# Bf706_DSP.net
KiCad netlist of a schematic drawn in Altium Designer
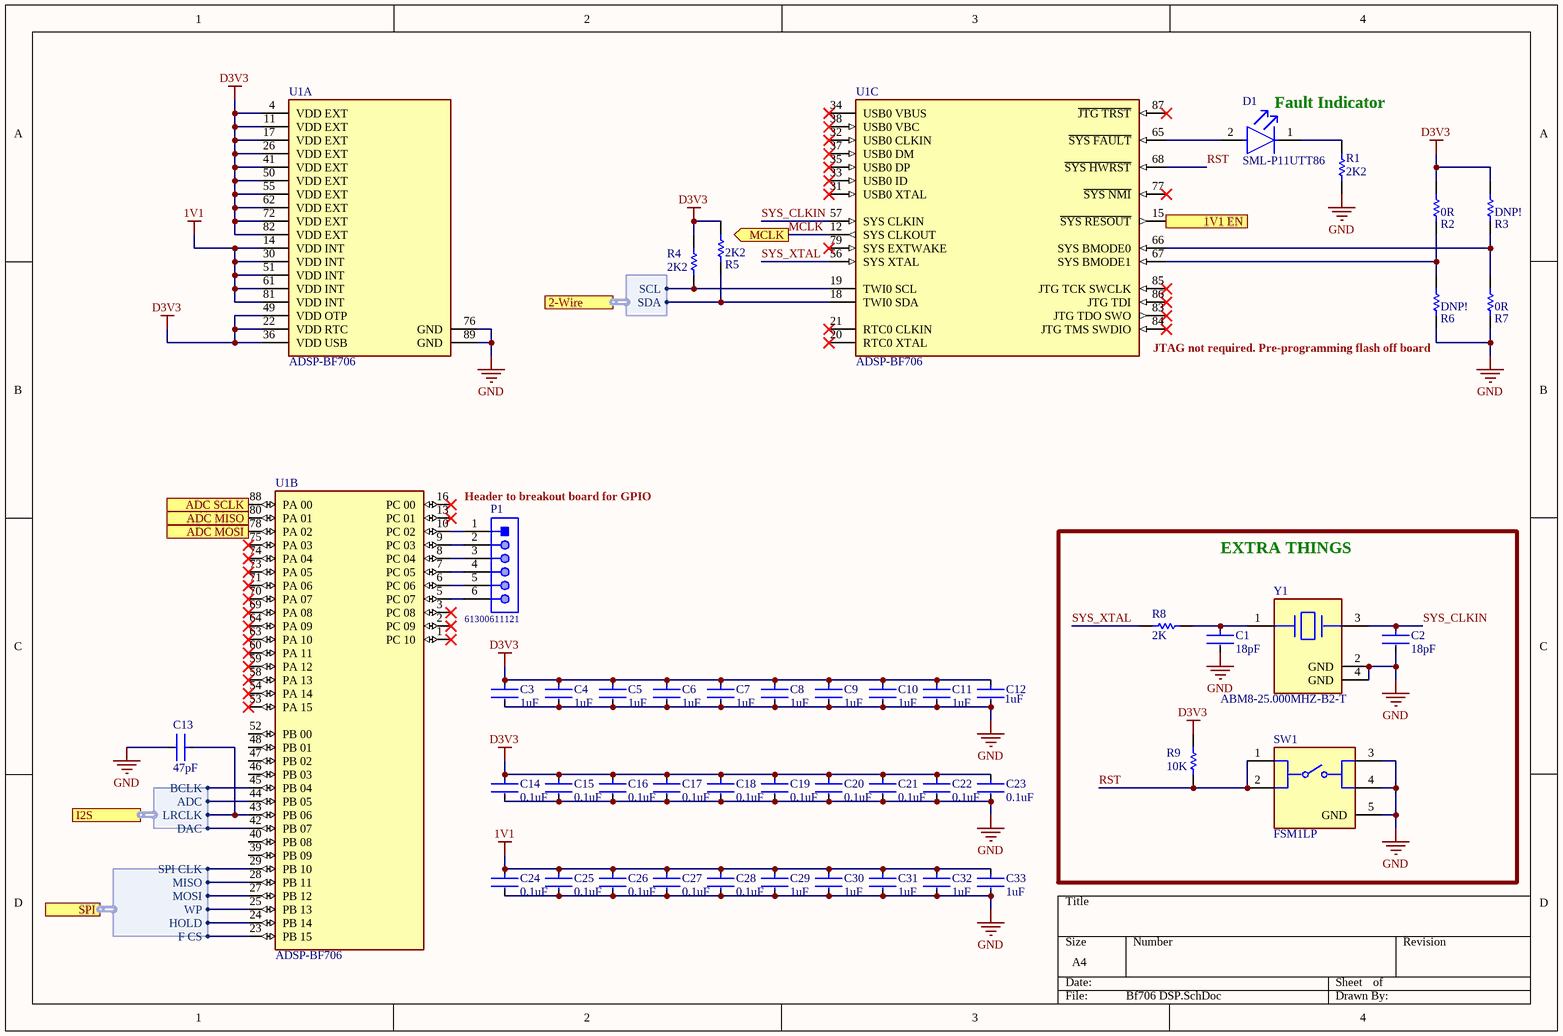
[diagram p0: Bf706 DSP.SchDoc]

(export (version "E")
  (design (tool "Eeschema 10.0.6"))
  (components
    (comp (ref "C1")
      (value "18pF")
      (footprint "FP-GRM15-MFG")
      (description "CAP CER 0.1UF 16V X7R 0402")
      (fields (field (name "MANUFACTURER PART NUMBER") "GRM155R71C104KA88D") (field (name "TOLERANCE") "10%"))
      (libsource (lib "Altium Content Vault") (part "236180d848d6139a670b325ea6854c9"))
    )
    (comp (ref "C2")
      (value "18pF")
      (footprint "FP-GRM15-MFG")
      (description "CAP CER 0.1UF 16V X7R 0402")
      (fields (field (name "MANUFACTURER PART NUMBER") "GRM155R71C104KA88D") (field (name "TOLERANCE") "10%"))
      (libsource (lib "Altium Content Vault") (part "236180d848d6139a670b325ea6854c9"))
    )
    (comp (ref "C3")
      (value "1uF")
      (footprint "FP-GRM15-MFG")
      (description "CAP CER 0.1UF 16V X7R 0402")
      (fields (field (name "MANUFACTURER PART NUMBER") "GRM155R71C104KA88D") (field (name "TOLERANCE") "10%"))
      (libsource (lib "Altium Content Vault") (part "236180d848d6139a670b325ea6854c9"))
    )
    (comp (ref "C4")
      (value "1uF")
      (footprint "FP-GRM15-MFG")
      (description "CAP CER 0.1UF 16V X7R 0402")
      (fields (field (name "MANUFACTURER PART NUMBER") "GRM155R71C104KA88D") (field (name "TOLERANCE") "10%"))
      (libsource (lib "Altium Content Vault") (part "236180d848d6139a670b325ea6854c9"))
    )
    (comp (ref "C5")
      (value "1uF")
      (footprint "FP-GRM15-MFG")
      (description "CAP CER 0.1UF 16V X7R 0402")
      (fields (field (name "MANUFACTURER PART NUMBER") "GRM155R71C104KA88D") (field (name "TOLERANCE") "10%"))
      (libsource (lib "Altium Content Vault") (part "236180d848d6139a670b325ea6854c9"))
    )
    (comp (ref "C6")
      (value "1uF")
      (footprint "FP-GRM15-MFG")
      (description "CAP CER 0.1UF 16V X7R 0402")
      (fields (field (name "MANUFACTURER PART NUMBER") "GRM155R71C104KA88D") (field (name "TOLERANCE") "10%"))
      (libsource (lib "Altium Content Vault") (part "236180d848d6139a670b325ea6854c9"))
    )
    (comp (ref "C7")
      (value "1uF")
      (footprint "FP-GRM15-MFG")
      (description "CAP CER 0.1UF 16V X7R 0402")
      (fields (field (name "MANUFACTURER PART NUMBER") "GRM155R71C104KA88D") (field (name "TOLERANCE") "10%"))
      (libsource (lib "Altium Content Vault") (part "236180d848d6139a670b325ea6854c9"))
    )
    (comp (ref "C8")
      (value "1uF")
      (footprint "FP-GRM15-MFG")
      (description "CAP CER 0.1UF 16V X7R 0402")
      (fields (field (name "MANUFACTURER PART NUMBER") "GRM155R71C104KA88D") (field (name "TOLERANCE") "10%"))
      (libsource (lib "Altium Content Vault") (part "236180d848d6139a670b325ea6854c9"))
    )
    (comp (ref "C9")
      (value "1uF")
      (footprint "FP-GRM15-MFG")
      (description "CAP CER 0.1UF 16V X7R 0402")
      (fields (field (name "MANUFACTURER PART NUMBER") "GRM155R71C104KA88D") (field (name "TOLERANCE") "10%"))
      (libsource (lib "Altium Content Vault") (part "236180d848d6139a670b325ea6854c9"))
    )
    (comp (ref "C10")
      (value "1uF")
      (footprint "FP-GRM15-MFG")
      (description "CAP CER 0.1UF 16V X7R 0402")
      (fields (field (name "MANUFACTURER PART NUMBER") "GRM155R71C104KA88D") (field (name "TOLERANCE") "10%"))
      (libsource (lib "Altium Content Vault") (part "236180d848d6139a670b325ea6854c9"))
    )
    (comp (ref "C11")
      (value "1uF")
      (footprint "FP-GRM15-MFG")
      (description "CAP CER 0.1UF 16V X7R 0402")
      (fields (field (name "MANUFACTURER PART NUMBER") "GRM155R71C104KA88D") (field (name "TOLERANCE") "10%"))
      (libsource (lib "Altium Content Vault") (part "236180d848d6139a670b325ea6854c9"))
    )
    (comp (ref "C12")
      (value "1uF")
      (footprint "FP-GRM15-MFG")
      (description "CAP CER 0.1UF 16V X7R 0402")
      (fields (field (name "MANUFACTURER PART NUMBER") "GRM155R71C104KA88D") (field (name "TOLERANCE") "10%"))
      (libsource (lib "Altium Content Vault") (part "236180d848d6139a670b325ea6854c9"))
    )
    (comp (ref "C13")
      (value "47pF")
      (footprint "FP-GRM15-MFG")
      (description "CAP CER 0.1UF 16V X7R 0402")
      (fields (field (name "MANUFACTURER PART NUMBER") "GRM155R71C104KA88D") (field (name "TOLERANCE") "10%"))
      (libsource (lib "Altium Content Vault") (part "236180d848d6139a670b325ea6854c9"))
    )
    (comp (ref "C14")
      (value "0.1uF")
      (footprint "FP-GRM15-MFG")
      (description "CAP CER 0.1UF 16V X7R 0402")
      (fields (field (name "MANUFACTURER PART NUMBER") "GRM155R71C104KA88D") (field (name "TOLERANCE") "10%"))
      (libsource (lib "Altium Content Vault") (part "236180d848d6139a670b325ea6854c9"))
    )
    (comp (ref "C15")
      (value "0.1uF")
      (footprint "FP-GRM15-MFG")
      (description "CAP CER 0.1UF 16V X7R 0402")
      (fields (field (name "MANUFACTURER PART NUMBER") "GRM155R71C104KA88D") (field (name "TOLERANCE") "10%"))
      (libsource (lib "Altium Content Vault") (part "236180d848d6139a670b325ea6854c9"))
    )
    (comp (ref "C16")
      (value "0.1uF")
      (footprint "FP-GRM15-MFG")
      (description "CAP CER 0.1UF 16V X7R 0402")
      (fields (field (name "MANUFACTURER PART NUMBER") "GRM155R71C104KA88D") (field (name "TOLERANCE") "10%"))
      (libsource (lib "Altium Content Vault") (part "236180d848d6139a670b325ea6854c9"))
    )
    (comp (ref "C17")
      (value "0.1uF")
      (footprint "FP-GRM15-MFG")
      (description "CAP CER 0.1UF 16V X7R 0402")
      (fields (field (name "MANUFACTURER PART NUMBER") "GRM155R71C104KA88D") (field (name "TOLERANCE") "10%"))
      (libsource (lib "Altium Content Vault") (part "236180d848d6139a670b325ea6854c9"))
    )
    (comp (ref "C18")
      (value "0.1uF")
      (footprint "FP-GRM15-MFG")
      (description "CAP CER 0.1UF 16V X7R 0402")
      (fields (field (name "MANUFACTURER PART NUMBER") "GRM155R71C104KA88D") (field (name "TOLERANCE") "10%"))
      (libsource (lib "Altium Content Vault") (part "236180d848d6139a670b325ea6854c9"))
    )
    (comp (ref "C19")
      (value "0.1uF")
      (footprint "FP-GRM15-MFG")
      (description "CAP CER 0.1UF 16V X7R 0402")
      (fields (field (name "MANUFACTURER PART NUMBER") "GRM155R71C104KA88D") (field (name "TOLERANCE") "10%"))
      (libsource (lib "Altium Content Vault") (part "236180d848d6139a670b325ea6854c9"))
    )
    (comp (ref "C20")
      (value "0.1uF")
      (footprint "FP-GRM15-MFG")
      (description "CAP CER 0.1UF 16V X7R 0402")
      (fields (field (name "MANUFACTURER PART NUMBER") "GRM155R71C104KA88D") (field (name "TOLERANCE") "10%"))
      (libsource (lib "Altium Content Vault") (part "236180d848d6139a670b325ea6854c9"))
    )
    (comp (ref "C21")
      (value "0.1uF")
      (footprint "FP-GRM15-MFG")
      (description "CAP CER 0.1UF 16V X7R 0402")
      (fields (field (name "MANUFACTURER PART NUMBER") "GRM155R71C104KA88D") (field (name "TOLERANCE") "10%"))
      (libsource (lib "Altium Content Vault") (part "236180d848d6139a670b325ea6854c9"))
    )
    (comp (ref "C22")
      (value "0.1uF")
      (footprint "FP-GRM15-MFG")
      (description "CAP CER 0.1UF 16V X7R 0402")
      (fields (field (name "MANUFACTURER PART NUMBER") "GRM155R71C104KA88D") (field (name "TOLERANCE") "10%"))
      (libsource (lib "Altium Content Vault") (part "236180d848d6139a670b325ea6854c9"))
    )
    (comp (ref "C23")
      (value "0.1uF")
      (footprint "FP-GRM15-MFG")
      (description "CAP CER 0.1UF 16V X7R 0402")
      (fields (field (name "MANUFACTURER PART NUMBER") "GRM155R71C104KA88D") (field (name "TOLERANCE") "10%"))
      (libsource (lib "Altium Content Vault") (part "236180d848d6139a670b325ea6854c9"))
    )
    (comp (ref "C24")
      (value "0.1uF")
      (footprint "FP-GRM15-MFG")
      (description "CAP CER 0.1UF 16V X7R 0402")
      (fields (field (name "MANUFACTURER PART NUMBER") "GRM155R71C104KA88D") (field (name "TOLERANCE") "10%"))
      (libsource (lib "Altium Content Vault") (part "236180d848d6139a670b325ea6854c9"))
    )
    (comp (ref "C25")
      (value "0.1uF")
      (footprint "FP-GRM15-MFG")
      (description "CAP CER 0.1UF 16V X7R 0402")
      (fields (field (name "MANUFACTURER PART NUMBER") "GRM155R71C104KA88D") (field (name "TOLERANCE") "10%"))
      (libsource (lib "Altium Content Vault") (part "236180d848d6139a670b325ea6854c9"))
    )
    (comp (ref "C26")
      (value "0.1uF")
      (footprint "FP-GRM15-MFG")
      (description "CAP CER 0.1UF 16V X7R 0402")
      (fields (field (name "MANUFACTURER PART NUMBER") "GRM155R71C104KA88D") (field (name "TOLERANCE") "10%"))
      (libsource (lib "Altium Content Vault") (part "236180d848d6139a670b325ea6854c9"))
    )
    (comp (ref "C27")
      (value "0.1uF")
      (footprint "FP-GRM15-MFG")
      (description "CAP CER 0.1UF 16V X7R 0402")
      (fields (field (name "MANUFACTURER PART NUMBER") "GRM155R71C104KA88D") (field (name "TOLERANCE") "10%"))
      (libsource (lib "Altium Content Vault") (part "236180d848d6139a670b325ea6854c9"))
    )
    (comp (ref "C28")
      (value "0.1uF")
      (footprint "FP-GRM15-MFG")
      (description "CAP CER 0.1UF 16V X7R 0402")
      (fields (field (name "MANUFACTURER PART NUMBER") "GRM155R71C104KA88D") (field (name "TOLERANCE") "10%"))
      (libsource (lib "Altium Content Vault") (part "236180d848d6139a670b325ea6854c9"))
    )
    (comp (ref "C29")
      (value "1uF")
      (footprint "FP-GRM15-MFG")
      (description "CAP CER 0.1UF 16V X7R 0402")
      (fields (field (name "MANUFACTURER PART NUMBER") "GRM155R71C104KA88D") (field (name "TOLERANCE") "10%"))
      (libsource (lib "Altium Content Vault") (part "236180d848d6139a670b325ea6854c9"))
    )
    (comp (ref "C30")
      (value "1uF")
      (footprint "FP-GRM15-MFG")
      (description "CAP CER 0.1UF 16V X7R 0402")
      (fields (field (name "MANUFACTURER PART NUMBER") "GRM155R71C104KA88D") (field (name "TOLERANCE") "10%"))
      (libsource (lib "Altium Content Vault") (part "236180d848d6139a670b325ea6854c9"))
    )
    (comp (ref "C31")
      (value "1uF")
      (footprint "FP-GRM15-MFG")
      (description "CAP CER 0.1UF 16V X7R 0402")
      (fields (field (name "MANUFACTURER PART NUMBER") "GRM155R71C104KA88D") (field (name "TOLERANCE") "10%"))
      (libsource (lib "Altium Content Vault") (part "236180d848d6139a670b325ea6854c9"))
    )
    (comp (ref "C32")
      (value "1uF")
      (footprint "FP-GRM15-MFG")
      (description "CAP CER 0.1UF 16V X7R 0402")
      (fields (field (name "MANUFACTURER PART NUMBER") "GRM155R71C104KA88D") (field (name "TOLERANCE") "10%"))
      (libsource (lib "Altium Content Vault") (part "236180d848d6139a670b325ea6854c9"))
    )
    (comp (ref "C33")
      (value "1uF")
      (footprint "FP-GRM15-MFG")
      (description "CAP CER 0.1UF 16V X7R 0402")
      (fields (field (name "MANUFACTURER PART NUMBER") "GRM155R71C104KA88D") (field (name "TOLERANCE") "10%"))
      (libsource (lib "Altium Content Vault") (part "236180d848d6139a670b325ea6854c9"))
    )
    (comp (ref "D1")
      (value "SML-P11UTT86")
      (footprint "FP-SML-P11UTT86-MFG")
      (description "LED RED CLEAR 1006 SMD")
      (libsource (lib "Altium Content Vault") (part "8706943c75ba83719d021d2fdc84c58"))
    )
    (comp (ref "P1")
      (value "61300611121")
      (footprint "61300611121")
      (description "THT Vertical Pin Header WR-PHD, Pitch 2.54 mm, Single Row, 6 pins")
      (fields (field (name "MANUFACTURER") "Wurth Elektronik") (field (name "PUBLISHER") "WurthElektronik"))
      (libsource (lib "Altium Content Vault") (part "WE-CN-1P-M-R6"))
    )
    (comp (ref "R1")
      (value "2K2")
      (footprint "RESC1005X40X25LL05T05")
      (description "Chip Resistor, 0 Ohm, 0.1 W, -55 to 155 degC, 0402 (1005 Metric), RoHS, Tape and Reel")
      (fields (field (name "MANUFACTURER") "Panasonic") (field (name "TOLERANCE") "5%"))
      (libsource (lib "Altium Content Vault") (part "RES-2"))
    )
    (comp (ref "R2")
      (value "0R")
      (footprint "RESC1005X40X25LL05T05")
      (description "Chip Resistor, 0 Ohm, 0.1 W, -55 to 155 degC, 0402 (1005 Metric), RoHS, Tape and Reel")
      (fields (field (name "MANUFACTURER") "Panasonic") (field (name "TOLERANCE") "5%"))
      (libsource (lib "Altium Content Vault") (part "RES-2"))
    )
    (comp (ref "R3")
      (value "DNP!")
      (footprint "RESC1005X40X25LL05T05")
      (description "Chip Resistor, 0 Ohm, 0.1 W, -55 to 155 degC, 0402 (1005 Metric), RoHS, Tape and Reel")
      (fields (field (name "MANUFACTURER") "Panasonic") (field (name "TOLERANCE") "5%"))
      (libsource (lib "Altium Content Vault") (part "RES-2"))
    )
    (comp (ref "R4")
      (value "2K2")
      (footprint "RESC1005X40X25LL05T05")
      (description "Chip Resistor, 0 Ohm, 0.1 W, -55 to 155 degC, 0402 (1005 Metric), RoHS, Tape and Reel")
      (fields (field (name "MANUFACTURER") "Panasonic") (field (name "TOLERANCE") "5%"))
      (libsource (lib "Altium Content Vault") (part "RES-2"))
    )
    (comp (ref "R5")
      (value "2K2")
      (footprint "RESC1005X40X25LL05T05")
      (description "Chip Resistor, 0 Ohm, 0.1 W, -55 to 155 degC, 0402 (1005 Metric), RoHS, Tape and Reel")
      (fields (field (name "MANUFACTURER") "Panasonic") (field (name "TOLERANCE") "5%"))
      (libsource (lib "Altium Content Vault") (part "RES-2"))
    )
    (comp (ref "R6")
      (value "DNP!")
      (footprint "RESC1005X40X25LL05T05")
      (description "Chip Resistor, 0 Ohm, 0.1 W, -55 to 155 degC, 0402 (1005 Metric), RoHS, Tape and Reel")
      (fields (field (name "MANUFACTURER") "Panasonic") (field (name "TOLERANCE") "5%"))
      (libsource (lib "Altium Content Vault") (part "RES-2"))
    )
    (comp (ref "R7")
      (value "0R")
      (footprint "RESC1005X40X25LL05T05")
      (description "Chip Resistor, 0 Ohm, 0.1 W, -55 to 155 degC, 0402 (1005 Metric), RoHS, Tape and Reel")
      (fields (field (name "MANUFACTURER") "Panasonic") (field (name "TOLERANCE") "5%"))
      (libsource (lib "Altium Content Vault") (part "RES-2"))
    )
    (comp (ref "R8")
      (value "2K")
      (footprint "RESC1005X40X25LL05T05")
      (description "Chip Resistor, 0 Ohm, 0.1 W, -55 to 155 degC, 0402 (1005 Metric), RoHS, Tape and Reel")
      (fields (field (name "MANUFACTURER") "Panasonic") (field (name "TOLERANCE") "5%"))
      (libsource (lib "Altium Content Vault") (part "RES-2"))
    )
    (comp (ref "R9")
      (value "10K")
      (footprint "RESC1005X40X25LL05T05")
      (description "Chip Resistor, 0 Ohm, 0.1 W, -55 to 155 degC, 0402 (1005 Metric), RoHS, Tape and Reel")
      (fields (field (name "MANUFACTURER") "Panasonic") (field (name "TOLERANCE") "5%"))
      (libsource (lib "Altium Content Vault") (part "RES-2"))
    )
    (comp (ref "SW1")
      (value "FSM1LP")
      (footprint "FP-FSM1LP-MFG")
      (description "SWITCH TACTILE SPST-NO 0.05A 24V")
      (libsource (lib "Altium Content Vault") (part "3a9e64be5c1b186b34f28721102267a"))
    )
    (comp (ref "U1")
      (value "ADSP-BF706")
      (footprint "FP-CP-88-8-IPC_C")
      (description "IC DSP LP 128KB L2SR 88LFCSP")
      (libsource (lib "Altium Content Vault") (part "f148b48c6e4e4aed1bc29808ef88166"))
    )
    (comp (ref "Y1")
      (value "ABM8-25.000MHZ-B2-T")
      (footprint "FP-ABM8-MFG")
      (description "Crystal 25MHz ±20ppm 18pF SMD-4 3.2mm x 2.5mm")
      (fields (field (name "TOLERANCE") "20ppm"))
      (libsource (lib "Altium Content Vault") (part "dfdb7f9a12507849fb681da9a70121c"))
    )
  )
  (nets
    (net (code "5") (name "/1V1 EN") (class "Default")
      (node (ref "U1") (pin "15") (pinfunction "~{SYS_RESOUT}_15") (pintype "output"))
    )
    (net (code "6") (name "/ADC") (class "Default")
      (node (ref "U1") (pin "44") (pinfunction "PB_05_44") (pintype "bidirectional"))
    )
    (net (code "7") (name "/ADC MISO") (class "Default")
      (node (ref "U1") (pin "80") (pinfunction "PA_01_80") (pintype "bidirectional"))
    )
    (net (code "8") (name "/ADC MOSI") (class "Default")
      (node (ref "U1") (pin "78") (pinfunction "PA_02_78") (pintype "bidirectional"))
    )
    (net (code "9") (name "/ADC SCLK") (class "Default")
      (node (ref "U1") (pin "88") (pinfunction "PA_00_88") (pintype "bidirectional"))
    )
    (net (code "10") (name "/BCLK") (class "Default")
      (node (ref "U1") (pin "45") (pinfunction "PB_04_45") (pintype "bidirectional"))
    )
    (net (code "11") (name "/DAC") (class "Default")
      (node (ref "U1") (pin "42") (pinfunction "PB_07_42") (pintype "bidirectional"))
    )
    (net (code "12") (name "/F CS") (class "Default")
      (node (ref "U1") (pin "23") (pinfunction "PB_15_23") (pintype "bidirectional"))
    )
    (net (code "13") (name "/HOLD") (class "Default")
      (node (ref "U1") (pin "24") (pinfunction "PB_14_24") (pintype "bidirectional"))
    )
    (net (code "14") (name "/LRCLK") (class "Default")
      (node (ref "C13") (pin "2") (pinfunction "2_2") (pintype "passive"))
      (node (ref "U1") (pin "43") (pinfunction "PB_06_43") (pintype "bidirectional"))
    )
    (net (code "15") (name "/MCLK") (class "Default")
      (node (ref "U1") (pin "12") (pinfunction "SYS_CLKOUT_12") (pintype "output"))
    )
    (net (code "16") (name "/MISO") (class "Default")
      (node (ref "U1") (pin "28") (pinfunction "PB_11_28") (pintype "bidirectional"))
    )
    (net (code "17") (name "/MOSI") (class "Default")
      (node (ref "U1") (pin "27") (pinfunction "PB_12_27") (pintype "bidirectional"))
    )
    (net (code "18") (name "/RST") (class "Default")
      (node (ref "R9") (pin "1") (pinfunction "1_1") (pintype "passive"))
      (node (ref "SW1") (pin "1") (pinfunction "1_1") (pintype "passive"))
      (node (ref "SW1") (pin "2") (pinfunction "2_2") (pintype "passive"))
      (node (ref "U1") (pin "68") (pinfunction "~{SYS_HWRST}_68") (pintype "input"))
    )
    (net (code "19") (name "/SCL") (class "Default")
      (node (ref "R4") (pin "1") (pinfunction "1_1") (pintype "passive"))
      (node (ref "U1") (pin "19") (pinfunction "TWI0_SCL_19") (pintype "passive"))
    )
    (net (code "20") (name "/SDA") (class "Default")
      (node (ref "R5") (pin "1") (pinfunction "1_1") (pintype "passive"))
      (node (ref "U1") (pin "18") (pinfunction "TWI0_SDA_18") (pintype "passive"))
    )
    (net (code "21") (name "/SPI CLK") (class "Default")
      (node (ref "U1") (pin "29") (pinfunction "PB_10_29") (pintype "bidirectional"))
    )
    (net (code "22") (name "/SYS_CLKIN") (class "Default")
      (node (ref "C2") (pin "2") (pinfunction "2_2") (pintype "passive"))
      (node (ref "U1") (pin "57") (pinfunction "SYS_CLKIN_57") (pintype "input"))
      (node (ref "Y1") (pin "3") (pinfunction "3_3") (pintype "passive"))
    )
    (net (code "23") (name "/SYS_XTAL") (class "Default")
      (node (ref "R8") (pin "2") (pinfunction "2_2") (pintype "passive"))
      (node (ref "U1") (pin "56") (pinfunction "SYS_XTAL_56") (pintype "input"))
    )
    (net (code "24") (name "/WP") (class "Default")
      (node (ref "U1") (pin "25") (pinfunction "PB_13_25") (pintype "bidirectional"))
    )
    (net (code "28") (name "1V1") (class "Default")
      (node (ref "C24") (pin "2") (pinfunction "2_2") (pintype "passive"))
      (node (ref "C25") (pin "2") (pinfunction "2_2") (pintype "passive"))
      (node (ref "C26") (pin "2") (pinfunction "2_2") (pintype "passive"))
      (node (ref "C27") (pin "2") (pinfunction "2_2") (pintype "passive"))
      (node (ref "C28") (pin "2") (pinfunction "2_2") (pintype "passive"))
      (node (ref "C29") (pin "2") (pinfunction "2_2") (pintype "passive"))
      (node (ref "C30") (pin "2") (pinfunction "2_2") (pintype "passive"))
      (node (ref "C31") (pin "2") (pinfunction "2_2") (pintype "passive"))
      (node (ref "C32") (pin "2") (pinfunction "2_2") (pintype "passive"))
      (node (ref "C33") (pin "2") (pinfunction "2_2") (pintype "passive"))
      (node (ref "U1") (pin "14") (pinfunction "VDD_INT_14") (pintype "power_in"))
      (node (ref "U1") (pin "30") (pinfunction "VDD_INT_30") (pintype "power_in"))
      (node (ref "U1") (pin "51") (pinfunction "VDD_INT_51") (pintype "power_in"))
      (node (ref "U1") (pin "61") (pinfunction "VDD_INT_61") (pintype "power_in"))
      (node (ref "U1") (pin "81") (pinfunction "VDD_INT_81") (pintype "power_in"))
    )
    (net (code "29") (name "D3V3") (class "Default")
      (node (ref "C10") (pin "2") (pinfunction "2_2") (pintype "passive"))
      (node (ref "C11") (pin "2") (pinfunction "2_2") (pintype "passive"))
      (node (ref "C12") (pin "2") (pinfunction "2_2") (pintype "passive"))
      (node (ref "C14") (pin "2") (pinfunction "2_2") (pintype "passive"))
      (node (ref "C15") (pin "2") (pinfunction "2_2") (pintype "passive"))
      (node (ref "C16") (pin "2") (pinfunction "2_2") (pintype "passive"))
      (node (ref "C17") (pin "2") (pinfunction "2_2") (pintype "passive"))
      (node (ref "C18") (pin "2") (pinfunction "2_2") (pintype "passive"))
      (node (ref "C19") (pin "2") (pinfunction "2_2") (pintype "passive"))
      (node (ref "C20") (pin "2") (pinfunction "2_2") (pintype "passive"))
      (node (ref "C21") (pin "2") (pinfunction "2_2") (pintype "passive"))
      (node (ref "C22") (pin "2") (pinfunction "2_2") (pintype "passive"))
      (node (ref "C23") (pin "2") (pinfunction "2_2") (pintype "passive"))
      (node (ref "C3") (pin "2") (pinfunction "2_2") (pintype "passive"))
      (node (ref "C4") (pin "2") (pinfunction "2_2") (pintype "passive"))
      (node (ref "C5") (pin "2") (pinfunction "2_2") (pintype "passive"))
      (node (ref "C6") (pin "2") (pinfunction "2_2") (pintype "passive"))
      (node (ref "C7") (pin "2") (pinfunction "2_2") (pintype "passive"))
      (node (ref "C8") (pin "2") (pinfunction "2_2") (pintype "passive"))
      (node (ref "C9") (pin "2") (pinfunction "2_2") (pintype "passive"))
      (node (ref "R2") (pin "2") (pinfunction "2_2") (pintype "passive"))
      (node (ref "R3") (pin "2") (pinfunction "2_2") (pintype "passive"))
      (node (ref "R4") (pin "2") (pinfunction "2_2") (pintype "passive"))
      (node (ref "R5") (pin "2") (pinfunction "2_2") (pintype "passive"))
      (node (ref "R9") (pin "2") (pinfunction "2_2") (pintype "passive"))
      (node (ref "U1") (pin "11") (pinfunction "VDD_EXT_11") (pintype "power_in"))
      (node (ref "U1") (pin "17") (pinfunction "VDD_EXT_17") (pintype "power_in"))
      (node (ref "U1") (pin "22") (pinfunction "VDD_RTC_22") (pintype "power_in"))
      (node (ref "U1") (pin "26") (pinfunction "VDD_EXT_26") (pintype "power_in"))
      (node (ref "U1") (pin "36") (pinfunction "VDD_USB_36") (pintype "power_in"))
      (node (ref "U1") (pin "4") (pinfunction "VDD_EXT_4") (pintype "power_in"))
      (node (ref "U1") (pin "41") (pinfunction "VDD_EXT_41") (pintype "power_in"))
      (node (ref "U1") (pin "49") (pinfunction "VDD_OTP_49") (pintype "power_in"))
      (node (ref "U1") (pin "50") (pinfunction "VDD_EXT_50") (pintype "power_in"))
      (node (ref "U1") (pin "55") (pinfunction "VDD_EXT_55") (pintype "power_in"))
      (node (ref "U1") (pin "62") (pinfunction "VDD_EXT_62") (pintype "power_in"))
      (node (ref "U1") (pin "72") (pinfunction "VDD_EXT_72") (pintype "power_in"))
      (node (ref "U1") (pin "82") (pinfunction "VDD_EXT_82") (pintype "power_in"))
    )
    (net (code "30") (name "GND") (class "Default")
      (node (ref "C1") (pin "1") (pinfunction "1_1") (pintype "passive"))
      (node (ref "C10") (pin "1") (pinfunction "1_1") (pintype "passive"))
      (node (ref "C11") (pin "1") (pinfunction "1_1") (pintype "passive"))
      (node (ref "C12") (pin "1") (pinfunction "1_1") (pintype "passive"))
      (node (ref "C13") (pin "1") (pinfunction "1_1") (pintype "passive"))
      (node (ref "C14") (pin "1") (pinfunction "1_1") (pintype "passive"))
      (node (ref "C15") (pin "1") (pinfunction "1_1") (pintype "passive"))
      (node (ref "C16") (pin "1") (pinfunction "1_1") (pintype "passive"))
      (node (ref "C17") (pin "1") (pinfunction "1_1") (pintype "passive"))
      (node (ref "C18") (pin "1") (pinfunction "1_1") (pintype "passive"))
      (node (ref "C19") (pin "1") (pinfunction "1_1") (pintype "passive"))
      (node (ref "C2") (pin "1") (pinfunction "1_1") (pintype "passive"))
      (node (ref "C20") (pin "1") (pinfunction "1_1") (pintype "passive"))
      (node (ref "C21") (pin "1") (pinfunction "1_1") (pintype "passive"))
      (node (ref "C22") (pin "1") (pinfunction "1_1") (pintype "passive"))
      (node (ref "C23") (pin "1") (pinfunction "1_1") (pintype "passive"))
      (node (ref "C24") (pin "1") (pinfunction "1_1") (pintype "passive"))
      (node (ref "C25") (pin "1") (pinfunction "1_1") (pintype "passive"))
      (node (ref "C26") (pin "1") (pinfunction "1_1") (pintype "passive"))
      (node (ref "C27") (pin "1") (pinfunction "1_1") (pintype "passive"))
      (node (ref "C28") (pin "1") (pinfunction "1_1") (pintype "passive"))
      (node (ref "C29") (pin "1") (pinfunction "1_1") (pintype "passive"))
      (node (ref "C3") (pin "1") (pinfunction "1_1") (pintype "passive"))
      (node (ref "C30") (pin "1") (pinfunction "1_1") (pintype "passive"))
      (node (ref "C31") (pin "1") (pinfunction "1_1") (pintype "passive"))
      (node (ref "C32") (pin "1") (pinfunction "1_1") (pintype "passive"))
      (node (ref "C33") (pin "1") (pinfunction "1_1") (pintype "passive"))
      (node (ref "C4") (pin "1") (pinfunction "1_1") (pintype "passive"))
      (node (ref "C5") (pin "1") (pinfunction "1_1") (pintype "passive"))
      (node (ref "C6") (pin "1") (pinfunction "1_1") (pintype "passive"))
      (node (ref "C7") (pin "1") (pinfunction "1_1") (pintype "passive"))
      (node (ref "C8") (pin "1") (pinfunction "1_1") (pintype "passive"))
      (node (ref "C9") (pin "1") (pinfunction "1_1") (pintype "passive"))
      (node (ref "R1") (pin "1") (pinfunction "1_1") (pintype "passive"))
      (node (ref "R6") (pin "1") (pinfunction "1_1") (pintype "passive"))
      (node (ref "R7") (pin "1") (pinfunction "1_1") (pintype "passive"))
      (node (ref "SW1") (pin "3") (pinfunction "3_3") (pintype "passive"))
      (node (ref "SW1") (pin "4") (pinfunction "4_4") (pintype "passive"))
      (node (ref "SW1") (pin "5") (pinfunction "GND_5") (pintype "power_in"))
      (node (ref "U1") (pin "76") (pinfunction "GND_76") (pintype "power_in"))
      (node (ref "U1") (pin "89") (pinfunction "GND_89") (pintype "power_in"))
      (node (ref "Y1") (pin "2") (pinfunction "GND_2") (pintype "power_in"))
      (node (ref "Y1") (pin "4") (pinfunction "GND_4") (pintype "power_in"))
    )
    (net (code "31") (name "Net-(C1-Pad2)") (class "Default")
      (node (ref "C1") (pin "2") (pinfunction "2_2") (pintype "passive"))
      (node (ref "R8") (pin "1") (pinfunction "1_1") (pintype "passive"))
      (node (ref "Y1") (pin "1") (pinfunction "1_1") (pintype "passive"))
    )
    (net (code "32") (name "Net-(D1-A)") (class "Default")
      (node (ref "D1") (pin "2") (pinfunction "A_2") (pintype "passive"))
      (node (ref "U1") (pin "65") (pinfunction "~{SYS_FAULT}_65") (pintype "input"))
    )
    (net (code "33") (name "Net-(D1-C)") (class "Default")
      (node (ref "D1") (pin "1") (pinfunction "C_1") (pintype "passive"))
      (node (ref "R1") (pin "2") (pinfunction "2_2") (pintype "passive"))
    )
    (net (code "34") (name "Net-(U1B-PC_02)") (class "Default")
      (node (ref "P1") (pin "1") (pinfunction "1_1") (pintype "passive"))
      (node (ref "U1") (pin "10") (pinfunction "PC_02_10") (pintype "bidirectional"))
    )
    (net (code "35") (name "Net-(U1B-PC_03)") (class "Default")
      (node (ref "P1") (pin "2") (pinfunction "2_2") (pintype "passive"))
      (node (ref "U1") (pin "9") (pinfunction "PC_03_9") (pintype "bidirectional"))
    )
    (net (code "36") (name "Net-(U1B-PC_04)") (class "Default")
      (node (ref "P1") (pin "3") (pinfunction "3_3") (pintype "passive"))
      (node (ref "U1") (pin "8") (pinfunction "PC_04_8") (pintype "bidirectional"))
    )
    (net (code "37") (name "Net-(U1B-PC_05)") (class "Default")
      (node (ref "P1") (pin "4") (pinfunction "4_4") (pintype "passive"))
      (node (ref "U1") (pin "7") (pinfunction "PC_05_7") (pintype "bidirectional"))
    )
    (net (code "38") (name "Net-(U1B-PC_06)") (class "Default")
      (node (ref "P1") (pin "5") (pinfunction "5_5") (pintype "passive"))
      (node (ref "U1") (pin "6") (pinfunction "PC_06_6") (pintype "bidirectional"))
    )
    (net (code "39") (name "Net-(U1B-PC_07)") (class "Default")
      (node (ref "P1") (pin "6") (pinfunction "6_6") (pintype "passive"))
      (node (ref "U1") (pin "5") (pinfunction "PC_07_5") (pintype "bidirectional"))
    )
    (net (code "40") (name "Net-(U1C-SYS_BMODE0)") (class "Default")
      (node (ref "R3") (pin "1") (pinfunction "1_1") (pintype "passive"))
      (node (ref "R7") (pin "2") (pinfunction "2_2") (pintype "passive"))
      (node (ref "U1") (pin "66") (pinfunction "SYS_BMODE0_66") (pintype "input"))
    )
    (net (code "41") (name "Net-(U1C-SYS_BMODE1)") (class "Default")
      (node (ref "R2") (pin "1") (pinfunction "1_1") (pintype "passive"))
      (node (ref "R6") (pin "2") (pinfunction "2_2") (pintype "passive"))
      (node (ref "U1") (pin "67") (pinfunction "SYS_BMODE1_67") (pintype "input"))
    )
    (net (code "42") (name "unconnected-(U1B-PA_03-Pad75)") (class "Default")
      (node (ref "U1") (pin "75") (pinfunction "PA_03_75") (pintype "bidirectional+no_connect"))
    )
    (net (code "43") (name "unconnected-(U1B-PA_04-Pad74)") (class "Default")
      (node (ref "U1") (pin "74") (pinfunction "PA_04_74") (pintype "bidirectional+no_connect"))
    )
    (net (code "44") (name "unconnected-(U1B-PA_05-Pad73)") (class "Default")
      (node (ref "U1") (pin "73") (pinfunction "PA_05_73") (pintype "bidirectional+no_connect"))
    )
    (net (code "45") (name "unconnected-(U1B-PA_06-Pad71)") (class "Default")
      (node (ref "U1") (pin "71") (pinfunction "PA_06_71") (pintype "bidirectional+no_connect"))
    )
    (net (code "46") (name "unconnected-(U1B-PA_07-Pad70)") (class "Default")
      (node (ref "U1") (pin "70") (pinfunction "PA_07_70") (pintype "bidirectional+no_connect"))
    )
    (net (code "47") (name "unconnected-(U1B-PA_08-Pad69)") (class "Default")
      (node (ref "U1") (pin "69") (pinfunction "PA_08_69") (pintype "bidirectional+no_connect"))
    )
    (net (code "48") (name "unconnected-(U1B-PA_09-Pad64)") (class "Default")
      (node (ref "U1") (pin "64") (pinfunction "PA_09_64") (pintype "bidirectional+no_connect"))
    )
    (net (code "49") (name "unconnected-(U1B-PA_10-Pad63)") (class "Default")
      (node (ref "U1") (pin "63") (pinfunction "PA_10_63") (pintype "bidirectional+no_connect"))
    )
    (net (code "50") (name "unconnected-(U1B-PA_11-Pad60)") (class "Default")
      (node (ref "U1") (pin "60") (pinfunction "PA_11_60") (pintype "bidirectional+no_connect"))
    )
    (net (code "51") (name "unconnected-(U1B-PA_12-Pad59)") (class "Default")
      (node (ref "U1") (pin "59") (pinfunction "PA_12_59") (pintype "bidirectional+no_connect"))
    )
    (net (code "52") (name "unconnected-(U1B-PA_13-Pad58)") (class "Default")
      (node (ref "U1") (pin "58") (pinfunction "PA_13_58") (pintype "bidirectional+no_connect"))
    )
    (net (code "53") (name "unconnected-(U1B-PA_14-Pad54)") (class "Default")
      (node (ref "U1") (pin "54") (pinfunction "PA_14_54") (pintype "bidirectional+no_connect"))
    )
    (net (code "54") (name "unconnected-(U1B-PA_15-Pad53)") (class "Default")
      (node (ref "U1") (pin "53") (pinfunction "PA_15_53") (pintype "bidirectional+no_connect"))
    )
    (net (code "55") (name "unconnected-(U1B-PB_00-Pad52)") (class "Default")
      (node (ref "U1") (pin "52") (pinfunction "PB_00_52") (pintype "bidirectional"))
    )
    (net (code "56") (name "unconnected-(U1B-PB_01-Pad48)") (class "Default")
      (node (ref "U1") (pin "48") (pinfunction "PB_01_48") (pintype "bidirectional"))
    )
    (net (code "57") (name "unconnected-(U1B-PB_02-Pad47)") (class "Default")
      (node (ref "U1") (pin "47") (pinfunction "PB_02_47") (pintype "bidirectional"))
    )
    (net (code "58") (name "unconnected-(U1B-PB_03-Pad46)") (class "Default")
      (node (ref "U1") (pin "46") (pinfunction "PB_03_46") (pintype "bidirectional"))
    )
    (net (code "59") (name "unconnected-(U1B-PB_08-Pad40)") (class "Default")
      (node (ref "U1") (pin "40") (pinfunction "PB_08_40") (pintype "bidirectional"))
    )
    (net (code "60") (name "unconnected-(U1B-PB_09-Pad39)") (class "Default")
      (node (ref "U1") (pin "39") (pinfunction "PB_09_39") (pintype "bidirectional"))
    )
    (net (code "61") (name "unconnected-(U1B-PC_00-Pad16)") (class "Default")
      (node (ref "U1") (pin "16") (pinfunction "PC_00_16") (pintype "bidirectional+no_connect"))
    )
    (net (code "62") (name "unconnected-(U1B-PC_01-Pad13)") (class "Default")
      (node (ref "U1") (pin "13") (pinfunction "PC_01_13") (pintype "bidirectional+no_connect"))
    )
    (net (code "63") (name "unconnected-(U1B-PC_08-Pad3)") (class "Default")
      (node (ref "U1") (pin "3") (pinfunction "PC_08_3") (pintype "bidirectional+no_connect"))
    )
    (net (code "64") (name "unconnected-(U1B-PC_09-Pad2)") (class "Default")
      (node (ref "U1") (pin "2") (pinfunction "PC_09_2") (pintype "bidirectional+no_connect"))
    )
    (net (code "65") (name "unconnected-(U1B-PC_10-Pad1)") (class "Default")
      (node (ref "U1") (pin "1") (pinfunction "PC_10_1") (pintype "bidirectional+no_connect"))
    )
    (net (code "66") (name "unconnected-(U1C-JTG_TCK_SWCLK-Pad85)") (class "Default")
      (node (ref "U1") (pin "85") (pinfunction "JTG_TCK_SWCLK_85") (pintype "input+no_connect"))
    )
    (net (code "67") (name "unconnected-(U1C-JTG_TDI-Pad86)") (class "Default")
      (node (ref "U1") (pin "86") (pinfunction "JTG_TDI_86") (pintype "input+no_connect"))
    )
    (net (code "68") (name "unconnected-(U1C-JTG_TDO_SWO-Pad83)") (class "Default")
      (node (ref "U1") (pin "83") (pinfunction "JTG_TDO_SWO_83") (pintype "output+no_connect"))
    )
    (net (code "69") (name "unconnected-(U1C-JTG_TMS_SWDIO-Pad84)") (class "Default")
      (node (ref "U1") (pin "84") (pinfunction "JTG_TMS_SWDIO_84") (pintype "input+no_connect"))
    )
    (net (code "70") (name "unconnected-(U1C-RTC0_CLKIN-Pad21)") (class "Default")
      (node (ref "U1") (pin "21") (pinfunction "RTC0_CLKIN_21") (pintype "passive+no_connect"))
    )
    (net (code "71") (name "unconnected-(U1C-RTC0_XTAL-Pad20)") (class "Default")
      (node (ref "U1") (pin "20") (pinfunction "RTC0_XTAL_20") (pintype "passive+no_connect"))
    )
    (net (code "72") (name "unconnected-(U1C-SYS_EXTWAKE-Pad79)") (class "Default")
      (node (ref "U1") (pin "79") (pinfunction "SYS_EXTWAKE_79") (pintype "input+no_connect"))
    )
    (net (code "73") (name "unconnected-(U1C-USB0_CLKIN-Pad32)") (class "Default")
      (node (ref "U1") (pin "32") (pinfunction "USB0_CLKIN_32") (pintype "input+no_connect"))
    )
    (net (code "74") (name "unconnected-(U1C-USB0_DM-Pad37)") (class "Default")
      (node (ref "U1") (pin "37") (pinfunction "USB0_DM_37") (pintype "input+no_connect"))
    )
    (net (code "75") (name "unconnected-(U1C-USB0_DP-Pad35)") (class "Default")
      (node (ref "U1") (pin "35") (pinfunction "USB0_DP_35") (pintype "input+no_connect"))
    )
    (net (code "76") (name "unconnected-(U1C-USB0_ID-Pad33)") (class "Default")
      (node (ref "U1") (pin "33") (pinfunction "USB0_ID_33") (pintype "input+no_connect"))
    )
    (net (code "77") (name "unconnected-(U1C-USB0_VBC-Pad38)") (class "Default")
      (node (ref "U1") (pin "38") (pinfunction "USB0_VBC_38") (pintype "input+no_connect"))
    )
    (net (code "78") (name "unconnected-(U1C-USB0_VBUS-Pad34)") (class "Default")
      (node (ref "U1") (pin "34") (pinfunction "USB0_VBUS_34") (pintype "power_in+no_connect"))
    )
    (net (code "79") (name "unconnected-(U1C-USB0_XTAL-Pad31)") (class "Default")
      (node (ref "U1") (pin "31") (pinfunction "USB0_XTAL_31") (pintype "input+no_connect"))
    )
    (net (code "80") (name "unconnected-(U1C-~{JTG_TRST}-Pad87)") (class "Default")
      (node (ref "U1") (pin "87") (pinfunction "~{JTG_TRST}_87") (pintype "input+no_connect"))
    )
    (net (code "81") (name "unconnected-(U1C-~{SYS_NMI}-Pad77)") (class "Default")
      (node (ref "U1") (pin "77") (pinfunction "~{SYS_NMI}_77") (pintype "input+no_connect"))
    )
  )
)
